# sparrow_v4_2.net
KiCad netlist of a schematic drawn in EAGLE
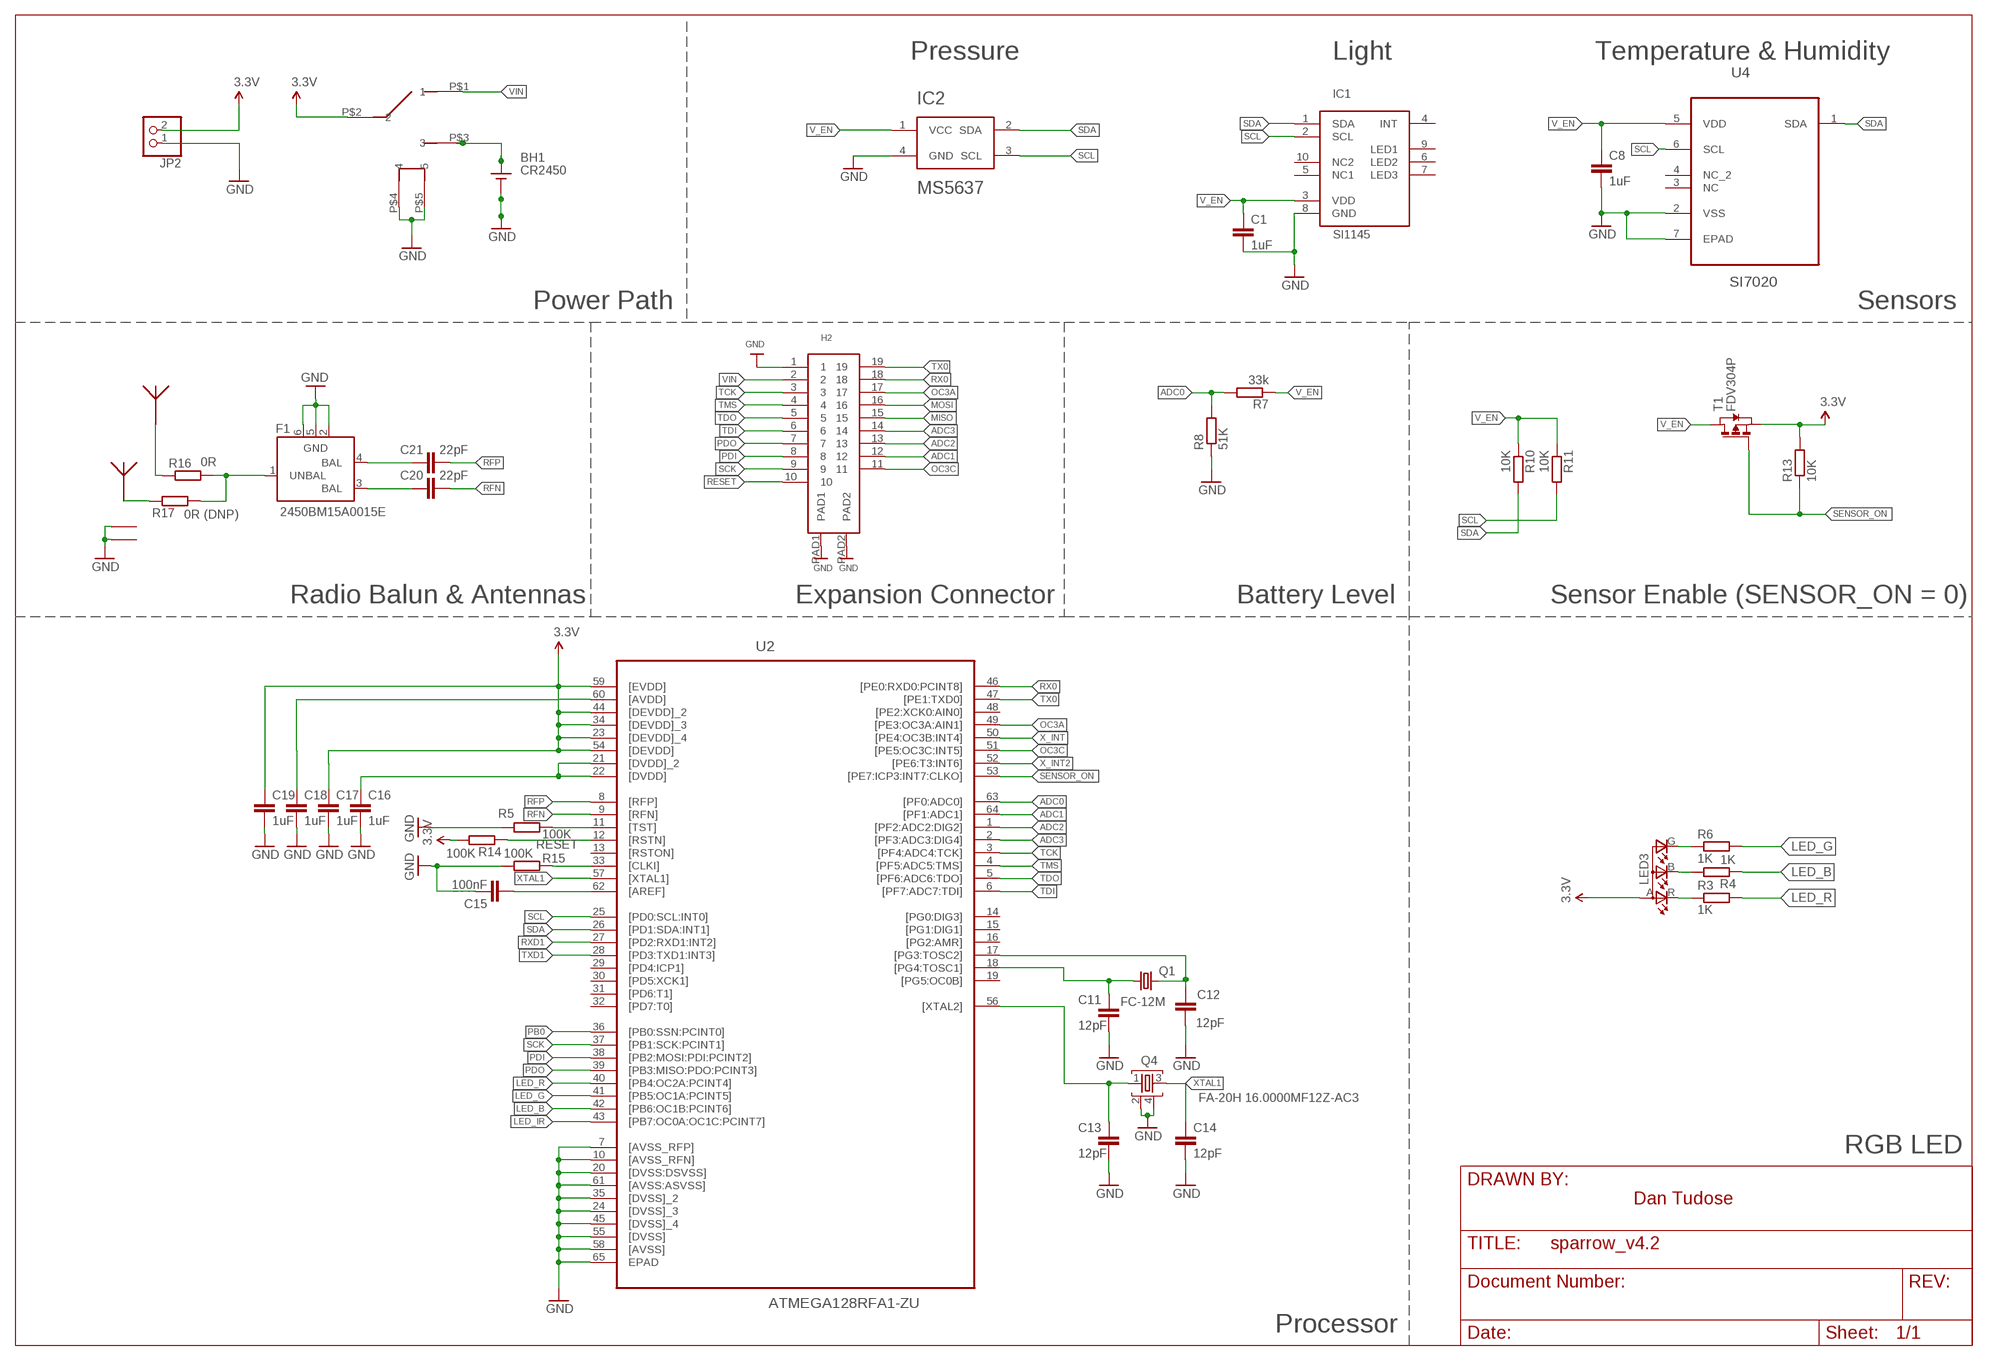
[diagram p0: schematic, sheet 1]

(export (version "E")
  (design (tool "Eeschema 10.0.6"))
  (components
    (comp (ref "C1")
      (value "1uF")
      (footprint "eagle-import:C0402")
      (libsource (lib "eagle-import") (part "C-EUC0402"))
    )
    (comp (ref "C8")
      (value "1uF")
      (footprint "eagle-import:C0402")
      (libsource (lib "eagle-import") (part "C-EUC0402"))
    )
    (comp (ref "C11")
      (value "12pF")
      (footprint "eagle-import:C0402")
      (libsource (lib "eagle-import") (part "C-EUC0402"))
    )
    (comp (ref "C12")
      (value "12pF")
      (footprint "eagle-import:C0402")
      (libsource (lib "eagle-import") (part "C-EUC0402"))
    )
    (comp (ref "C13")
      (value "12pF")
      (footprint "eagle-import:C0402")
      (libsource (lib "eagle-import") (part "C-EUC0402"))
    )
    (comp (ref "C14")
      (value "12pF")
      (footprint "eagle-import:C0402")
      (libsource (lib "eagle-import") (part "C-EUC0402"))
    )
    (comp (ref "C15")
      (value "100nF")
      (footprint "eagle-import:C0402")
      (libsource (lib "eagle-import") (part "C-EUC0402"))
    )
    (comp (ref "C16")
      (value "1uF")
      (footprint "eagle-import:C0402")
      (libsource (lib "eagle-import") (part "C-EUC0402"))
    )
    (comp (ref "C17")
      (value "1uF")
      (footprint "eagle-import:C0402")
      (libsource (lib "eagle-import") (part "C-EUC0402"))
    )
    (comp (ref "C18")
      (value "1uF")
      (footprint "eagle-import:C0402")
      (libsource (lib "eagle-import") (part "C-EUC0402"))
    )
    (comp (ref "C19")
      (value "1uF")
      (footprint "eagle-import:C0402")
      (libsource (lib "eagle-import") (part "C-EUC0402"))
    )
    (comp (ref "C20")
      (value "22pF")
      (footprint "eagle-import:C0402")
      (libsource (lib "eagle-import") (part "C-EUC0402"))
    )
    (comp (ref "C21")
      (value "22pF")
      (footprint "eagle-import:C0402")
      (libsource (lib "eagle-import") (part "C-EUC0402"))
    )
    (comp (ref "F1")
      (value "2450BM15A0015E")
      (footprint "eagle-import:2450BM15A0002")
      (libsource (lib "eagle-import") (part "2450BM15A0002"))
    )
    (comp (ref "H2")
      (value "DF9-19P-1V(32)")
      (footprint "eagle-import:DF9-19P-1V(32)")
      (libsource (lib "eagle-import") (part "DF9-19P-1V(32)"))
    )
    (comp (ref "IC1")
      (value "SI1145")
      (footprint "eagle-import:QFN10")
      (libsource (lib "eagle-import") (part "SI1145"))
    )
    (comp (ref "IC2")
      (value "MS5637")
      (footprint "eagle-import:MS5637")
      (libsource (lib "eagle-import") (part "MS5637"))
    )
    (comp (ref "JP2")
      (value "PINHD-1X2")
      (footprint "eagle-import:1X02")
      (libsource (lib "eagle-import") (part "PINHD-1X2"))
    )
    (comp (ref "LED3")
      (value "LED_RGB_CREE_PLCC4")
      (footprint "eagle-import:P-LCC-4-4")
      (libsource (lib "eagle-import") (part "LED_RGB_CREE_PLCC4"))
    )
    (comp (ref "Q1")
      (value "FC-12M")
      (footprint "eagle-import:FC-12M")
      (libsource (lib "eagle-import") (part "FC-12M"))
    )
    (comp (ref "Q4")
      (value "FA-20H 16.0000MF12Z-AC3")
      (footprint "eagle-import:FA-20H")
      (libsource (lib "eagle-import") (part "FA-20H"))
    )
    (comp (ref "R3")
      (value "1K")
      (footprint "eagle-import:R0402")
      (libsource (lib "eagle-import") (part "R-EU_R0402"))
    )
    (comp (ref "R4")
      (value "1K")
      (footprint "eagle-import:R0402")
      (libsource (lib "eagle-import") (part "R-EU_R0402"))
    )
    (comp (ref "R5")
      (value "100K")
      (footprint "eagle-import:R0402")
      (libsource (lib "eagle-import") (part "resistor_R-EU_R0402"))
    )
    (comp (ref "R6")
      (value "1K")
      (footprint "eagle-import:R0402")
      (libsource (lib "eagle-import") (part "R-EU_R0402"))
    )
    (comp (ref "R7")
      (value "33k")
      (footprint "eagle-import:R0402")
      (libsource (lib "eagle-import") (part "resistor_R-EU_R0402"))
    )
    (comp (ref "R8")
      (value "51K")
      (footprint "eagle-import:R0402")
      (libsource (lib "eagle-import") (part "resistor_R-EU_R0402"))
    )
    (comp (ref "R10")
      (value "10K")
      (footprint "eagle-import:R0402")
      (libsource (lib "eagle-import") (part "resistor_R-EU_R0402"))
    )
    (comp (ref "R11")
      (value "10K")
      (footprint "eagle-import:R0402")
      (libsource (lib "eagle-import") (part "resistor_R-EU_R0402"))
    )
    (comp (ref "R13")
      (value "10K")
      (footprint "eagle-import:R0402")
      (libsource (lib "eagle-import") (part "resistor_R-EU_R0402"))
    )
    (comp (ref "R14")
      (value "100K")
      (footprint "eagle-import:R0402")
      (libsource (lib "eagle-import") (part "resistor_R-EU_R0402"))
    )
    (comp (ref "R15")
      (value "100K")
      (footprint "eagle-import:R0402")
      (libsource (lib "eagle-import") (part "resistor_R-EU_R0402"))
    )
    (comp (ref "R16")
      (value "0R")
      (footprint "eagle-import:R0402")
      (libsource (lib "eagle-import") (part "resistor_R-EU_R0402"))
    )
    (comp (ref "R17")
      (value "0R (DNP)")
      (footprint "eagle-import:R0402")
      (libsource (lib "eagle-import") (part "resistor_R-EU_R0402"))
    )
    (comp (ref "T1")
      (value "FDV304P")
      (footprint "eagle-import:SOT-23")
      (libsource (lib "eagle-import") (part "PMOSSOT23"))
    )
    (comp (ref "U$1")
      (value "SWITCH")
      (footprint "eagle-import:PCM12")
      (libsource (lib "eagle-import") (part "SWITCH"))
    )
    (comp (ref "U1")
      (value "SMTU2450N-LF")
      (footprint "eagle-import:BATPACK")
      (libsource (lib "eagle-import") (part "RENATA_BAT"))
    )
    (comp (ref "U2")
      (value "ATMEGA128RFA1-ZU")
      (footprint "eagle-import:QFN50P900X900X90-64N")
      (libsource (lib "eagle-import") (part "ATMEGA128RFA1-ZU"))
    )
    (comp (ref "U4")
      (value "SI7020")
      (footprint "eagle-import:DFN300X300X110-7N")
      (fields (field (name "MPN") "SHT21"))
      (libsource (lib "eagle-import") (part "SHT21"))
    )
    (comp (ref "U8")
      (value "ANTENNA")
      (footprint "eagle-import:ANTPACK")
      (libsource (lib "eagle-import") (part "ANTENNA"))
    )
    (comp (ref "U10")
      (value "UFL-R-SMT")
      (footprint "eagle-import:U.FLPACK")
      (libsource (lib "eagle-import") (part "UFL-R-SMT"))
    )
  )
  (nets
    (net (code "1") (name "3.3V") (class "Default")
      (node (ref "C17") (pin "1") (pinfunction "1_1") (pintype "passive"))
      (node (ref "C19") (pin "1") (pinfunction "1_1") (pintype "passive"))
      (node (ref "JP2") (pin "2") (pinfunction "2_2") (pintype "passive"))
      (node (ref "LED3") (pin "A") (pinfunction "A2_A") (pintype "passive"))
      (node (ref "R13") (pin "2") (pinfunction "2_2") (pintype "passive"))
      (node (ref "R14") (pin "2") (pinfunction "2_2") (pintype "passive"))
      (node (ref "T1") (pin "2") (pinfunction "S_2") (pintype "passive"))
      (node (ref "U$1") (pin "P$2") (pinfunction "2_P$2") (pintype "bidirectional"))
      (node (ref "U2") (pin "23") (pinfunction "[DEVDD]_4_23") (pintype "power_in"))
      (node (ref "U2") (pin "34") (pinfunction "[DEVDD]_3_34") (pintype "power_in"))
      (node (ref "U2") (pin "44") (pinfunction "[DEVDD]_2_44") (pintype "power_in"))
      (node (ref "U2") (pin "54") (pinfunction "[DEVDD]_54") (pintype "power_in"))
      (node (ref "U2") (pin "59") (pinfunction "[EVDD]_59") (pintype "power_in"))
    )
    (net (code "2") (name "ADC0") (class "Default")
      (node (ref "R7") (pin "2") (pinfunction "2_2") (pintype "passive"))
      (node (ref "R8") (pin "2") (pinfunction "2_2") (pintype "passive"))
      (node (ref "U2") (pin "63") (pinfunction "[PF0:ADC0]_63") (pintype "bidirectional"))
    )
    (net (code "3") (name "ADC1") (class "Default")
      (node (ref "H2") (pin "12") (pinfunction "12_12") (pintype "bidirectional"))
      (node (ref "U2") (pin "64") (pinfunction "[PF1:ADC1]_64") (pintype "bidirectional"))
    )
    (net (code "4") (name "ADC2") (class "Default")
      (node (ref "H2") (pin "13") (pinfunction "13_13") (pintype "bidirectional"))
      (node (ref "U2") (pin "1") (pinfunction "[PF2:ADC2:DIG2]_1") (pintype "bidirectional"))
    )
    (net (code "5") (name "ADC3") (class "Default")
      (node (ref "H2") (pin "14") (pinfunction "14_14") (pintype "bidirectional"))
      (node (ref "U2") (pin "2") (pinfunction "[PF3:ADC3:DIG4]_2") (pintype "bidirectional"))
    )
    (net (code "6") (name "GND") (class "Default")
      (node (ref "C1") (pin "2") (pinfunction "2_2") (pintype "passive"))
      (node (ref "C11") (pin "2") (pinfunction "2_2") (pintype "passive"))
      (node (ref "C12") (pin "2") (pinfunction "2_2") (pintype "passive"))
      (node (ref "C13") (pin "2") (pinfunction "2_2") (pintype "passive"))
      (node (ref "C14") (pin "2") (pinfunction "2_2") (pintype "passive"))
      (node (ref "C15") (pin "1") (pinfunction "1_1") (pintype "passive"))
      (node (ref "C16") (pin "2") (pinfunction "2_2") (pintype "passive"))
      (node (ref "C17") (pin "2") (pinfunction "2_2") (pintype "passive"))
      (node (ref "C18") (pin "2") (pinfunction "2_2") (pintype "passive"))
      (node (ref "C19") (pin "2") (pinfunction "2_2") (pintype "passive"))
      (node (ref "C8") (pin "2") (pinfunction "2_2") (pintype "passive"))
      (node (ref "F1") (pin "2") (pinfunction "GND_2") (pintype "passive"))
      (node (ref "F1") (pin "5") (pinfunction "GND_5") (pintype "passive"))
      (node (ref "F1") (pin "6") (pinfunction "GND_6") (pintype "passive"))
      (node (ref "H2") (pin "1") (pinfunction "1_1") (pintype "bidirectional"))
      (node (ref "H2") (pin "PAD1") (pinfunction "PAD1_PAD1") (pintype "bidirectional"))
      (node (ref "H2") (pin "PAD2") (pinfunction "PAD2_PAD2") (pintype "bidirectional"))
      (node (ref "IC1") (pin "8") (pinfunction "GND_8") (pintype "bidirectional"))
      (node (ref "IC2") (pin "4") (pinfunction "GND_4") (pintype "bidirectional"))
      (node (ref "JP2") (pin "1") (pinfunction "1_1") (pintype "passive"))
      (node (ref "Q4") (pin "2") (pinfunction "2_2") (pintype "passive"))
      (node (ref "Q4") (pin "4") (pinfunction "4_4") (pintype "passive"))
      (node (ref "R15") (pin "2") (pinfunction "2_2") (pintype "passive"))
      (node (ref "R5") (pin "2") (pinfunction "2_2") (pintype "passive"))
      (node (ref "R8") (pin "1") (pinfunction "1_1") (pintype "passive"))
      (node (ref "U$1") (pin "P$4") (pinfunction "4_P$4") (pintype "bidirectional"))
      (node (ref "U$1") (pin "P$5") (pinfunction "5_P$5") (pintype "bidirectional"))
      (node (ref "U1") (pin "P$2") (pinfunction "P$2_P$2") (pintype "bidirectional"))
      (node (ref "U10") (pin "GND1") (pinfunction "P$3_GND1") (pintype "power_in"))
      (node (ref "U10") (pin "GND2") (pinfunction "P$2_GND2") (pintype "power_in"))
      (node (ref "U2") (pin "10") (pinfunction "[AVSS_RFN]_10") (pintype "power_in"))
      (node (ref "U2") (pin "20") (pinfunction "[DVSS:DSVSS]_20") (pintype "power_in"))
      (node (ref "U2") (pin "24") (pinfunction "[DVSS]_3_24") (pintype "power_in"))
      (node (ref "U2") (pin "35") (pinfunction "[DVSS]_2_35") (pintype "power_in"))
      (node (ref "U2") (pin "45") (pinfunction "[DVSS]_4_45") (pintype "power_in"))
      (node (ref "U2") (pin "55") (pinfunction "[DVSS]_55") (pintype "power_in"))
      (node (ref "U2") (pin "58") (pinfunction "[AVSS]_58") (pintype "power_in"))
      (node (ref "U2") (pin "61") (pinfunction "[AVSS:ASVSS]_61") (pintype "power_in"))
      (node (ref "U2") (pin "65") (pinfunction "EPAD_65") (pintype "passive"))
      (node (ref "U2") (pin "7") (pinfunction "[AVSS_RFP]_7") (pintype "power_in"))
      (node (ref "U4") (pin "2") (pinfunction "VSS_2") (pintype "power_in"))
      (node (ref "U4") (pin "7") (pinfunction "EPAD_7") (pintype "passive"))
    )
    (net (code "7") (name "LED_B") (class "Default")
      (node (ref "R4") (pin "1") (pinfunction "1_1") (pintype "passive"))
      (node (ref "U2") (pin "42") (pinfunction "[PB6:OC1B:PCINT6]_42") (pintype "bidirectional"))
    )
    (net (code "8") (name "LED_G") (class "Default")
      (node (ref "R6") (pin "2") (pinfunction "2_2") (pintype "passive"))
      (node (ref "U2") (pin "41") (pinfunction "[PB5:OC1A:PCINT5]_41") (pintype "bidirectional"))
    )
    (net (code "9") (name "LED_IR") (class "Default")
      (node (ref "U2") (pin "43") (pinfunction "[PB7:OC0A:OC1C:PCINT7]_43") (pintype "bidirectional"))
    )
    (net (code "10") (name "LED_R") (class "Default")
      (node (ref "R3") (pin "2") (pinfunction "2_2") (pintype "passive"))
      (node (ref "U2") (pin "40") (pinfunction "[PB4:OC2A:PCINT4]_40") (pintype "bidirectional"))
    )
    (net (code "11") (name "MISO") (class "Default")
      (node (ref "H2") (pin "15") (pinfunction "15_15") (pintype "bidirectional"))
    )
    (net (code "12") (name "MOSI") (class "Default")
      (node (ref "H2") (pin "16") (pinfunction "16_16") (pintype "bidirectional"))
    )
    (net (code "13") (name "Net-(C20-Pad1)") (class "Default")
      (node (ref "C20") (pin "1") (pinfunction "1_1") (pintype "passive"))
      (node (ref "F1") (pin "3") (pinfunction "BAL_3") (pintype "passive"))
    )
    (net (code "14") (name "Net-(C21-Pad1)") (class "Default")
      (node (ref "C21") (pin "1") (pinfunction "1_1") (pintype "passive"))
      (node (ref "F1") (pin "4") (pinfunction "BAL_4") (pintype "passive"))
    )
    (net (code "15") (name "Net-(F1-UNBAL)") (class "Default")
      (node (ref "F1") (pin "1") (pinfunction "UNBAL_1") (pintype "passive"))
      (node (ref "R16") (pin "2") (pinfunction "2_2") (pintype "passive"))
      (node (ref "R17") (pin "1") (pinfunction "1_1") (pintype "passive"))
    )
    (net (code "16") (name "Net-(LED3-CBLUE)") (class "Default")
      (node (ref "LED3") (pin "B") (pinfunction "CBLUE_B") (pintype "passive"))
      (node (ref "R4") (pin "2") (pinfunction "2_2") (pintype "passive"))
    )
    (net (code "17") (name "Net-(LED3-CGREEN)") (class "Default")
      (node (ref "LED3") (pin "G") (pinfunction "CGREEN_G") (pintype "passive"))
      (node (ref "R6") (pin "1") (pinfunction "1_1") (pintype "passive"))
    )
    (net (code "18") (name "Net-(LED3-CRED)") (class "Default")
      (node (ref "LED3") (pin "R") (pinfunction "CRED_R") (pintype "passive"))
      (node (ref "R3") (pin "1") (pinfunction "1_1") (pintype "passive"))
    )
    (net (code "19") (name "Net-(R16-Pad1)") (class "Default")
      (node (ref "R16") (pin "1") (pinfunction "1_1") (pintype "passive"))
      (node (ref "U8") (pin "P$1") (pinfunction "P$1_P$1") (pintype "bidirectional"))
    )
    (net (code "20") (name "Net-(R17-Pad2)") (class "Default")
      (node (ref "R17") (pin "2") (pinfunction "2_2") (pintype "passive"))
      (node (ref "U10") (pin "P$1") (pinfunction "P$1_P$1") (pintype "bidirectional"))
    )
    (net (code "21") (name "Net-(U$1-3)") (class "Default")
      (node (ref "U$1") (pin "P$3") (pinfunction "3_P$3") (pintype "bidirectional"))
      (node (ref "U1") (pin "P$1") (pinfunction "P$1_P$1") (pintype "bidirectional"))
    )
    (net (code "22") (name "Net-(U2-[AREF])") (class "Default")
      (node (ref "C15") (pin "2") (pinfunction "2_2") (pintype "passive"))
      (node (ref "U2") (pin "62") (pinfunction "[AREF]_62") (pintype "input"))
    )
    (net (code "23") (name "Net-(U2-[AVDD])") (class "Default")
      (node (ref "C18") (pin "1") (pinfunction "1_1") (pintype "passive"))
      (node (ref "U2") (pin "60") (pinfunction "[AVDD]_60") (pintype "power_in"))
    )
    (net (code "24") (name "Net-(U2-[CLKI])") (class "Default")
      (node (ref "R15") (pin "1") (pinfunction "1_1") (pintype "passive"))
      (node (ref "U2") (pin "33") (pinfunction "[CLKI]_33") (pintype "input"))
    )
    (net (code "25") (name "Net-(U2-[DVDD])") (class "Default")
      (node (ref "C16") (pin "1") (pinfunction "1_1") (pintype "passive"))
      (node (ref "U2") (pin "21") (pinfunction "[DVDD]_2_21") (pintype "power_in"))
      (node (ref "U2") (pin "22") (pinfunction "[DVDD]_22") (pintype "power_in"))
    )
    (net (code "26") (name "Net-(U2-[PG3:TOSC2])") (class "Default")
      (node (ref "C12") (pin "1") (pinfunction "1_1") (pintype "passive"))
      (node (ref "Q1") (pin "2") (pinfunction "2_2") (pintype "passive"))
      (node (ref "U2") (pin "17") (pinfunction "[PG3:TOSC2]_17") (pintype "bidirectional"))
    )
    (net (code "27") (name "Net-(U2-[PG4:TOSC1])") (class "Default")
      (node (ref "C11") (pin "1") (pinfunction "1_1") (pintype "passive"))
      (node (ref "Q1") (pin "1") (pinfunction "1_1") (pintype "passive"))
      (node (ref "U2") (pin "18") (pinfunction "[PG4:TOSC1]_18") (pintype "bidirectional"))
    )
    (net (code "28") (name "Net-(U2-[TST])") (class "Default")
      (node (ref "R5") (pin "1") (pinfunction "1_1") (pintype "passive"))
      (node (ref "U2") (pin "11") (pinfunction "[TST]_11") (pintype "input"))
    )
    (net (code "29") (name "Net-(U2-[XTAL2])") (class "Default")
      (node (ref "C13") (pin "1") (pinfunction "1_1") (pintype "passive"))
      (node (ref "Q4") (pin "1") (pinfunction "1_1") (pintype "passive"))
      (node (ref "U2") (pin "56") (pinfunction "[XTAL2]_56") (pintype "output"))
    )
    (net (code "30") (name "OC3A") (class "Default")
      (node (ref "H2") (pin "17") (pinfunction "17_17") (pintype "bidirectional"))
      (node (ref "U2") (pin "49") (pinfunction "[PE3:OC3A:AIN1]_49") (pintype "bidirectional"))
    )
    (net (code "31") (name "OC3C") (class "Default")
      (node (ref "H2") (pin "11") (pinfunction "11_11") (pintype "bidirectional"))
      (node (ref "U2") (pin "51") (pinfunction "[PE5:OC3C:INT5]_51") (pintype "bidirectional"))
    )
    (net (code "32") (name "PB0") (class "Default")
      (node (ref "U2") (pin "36") (pinfunction "[PB0:SSN:PCINT0]_36") (pintype "bidirectional"))
    )
    (net (code "33") (name "PDI") (class "Default")
      (node (ref "H2") (pin "8") (pinfunction "8_8") (pintype "bidirectional"))
      (node (ref "U2") (pin "38") (pinfunction "[PB2:MOSI:PDI:PCINT2]_38") (pintype "bidirectional"))
    )
    (net (code "34") (name "PDO") (class "Default")
      (node (ref "H2") (pin "7") (pinfunction "7_7") (pintype "bidirectional"))
      (node (ref "U2") (pin "39") (pinfunction "[PB3:MISO:PDO:PCINT3]_39") (pintype "bidirectional"))
    )
    (net (code "35") (name "RESET") (class "Default")
      (node (ref "H2") (pin "10") (pinfunction "10_10") (pintype "bidirectional"))
      (node (ref "R14") (pin "1") (pinfunction "1_1") (pintype "passive"))
      (node (ref "U2") (pin "12") (pinfunction "[RSTN]_12") (pintype "input"))
    )
    (net (code "36") (name "RFN") (class "Default")
      (node (ref "C20") (pin "2") (pinfunction "2_2") (pintype "passive"))
      (node (ref "U2") (pin "9") (pinfunction "[RFN]_9") (pintype "input"))
    )
    (net (code "37") (name "RFP") (class "Default")
      (node (ref "C21") (pin "2") (pinfunction "2_2") (pintype "passive"))
      (node (ref "U2") (pin "8") (pinfunction "[RFP]_8") (pintype "input"))
    )
    (net (code "38") (name "RX0") (class "Default")
      (node (ref "H2") (pin "18") (pinfunction "18_18") (pintype "bidirectional"))
      (node (ref "U2") (pin "46") (pinfunction "[PE0:RXD0:PCINT8]_46") (pintype "bidirectional"))
    )
    (net (code "39") (name "RXD1") (class "Default")
      (node (ref "U2") (pin "27") (pinfunction "[PD2:RXD1:INT2]_27") (pintype "bidirectional"))
    )
    (net (code "40") (name "SCK") (class "Default")
      (node (ref "H2") (pin "9") (pinfunction "9_9") (pintype "bidirectional"))
      (node (ref "U2") (pin "37") (pinfunction "[PB1:SCK:PCINT1]_37") (pintype "bidirectional"))
    )
    (net (code "41") (name "SCL") (class "Default")
      (node (ref "IC1") (pin "2") (pinfunction "SCL_2") (pintype "bidirectional"))
      (node (ref "IC2") (pin "3") (pinfunction "SCL_3") (pintype "bidirectional"))
      (node (ref "R11") (pin "2") (pinfunction "2_2") (pintype "passive"))
      (node (ref "U2") (pin "25") (pinfunction "[PD0:SCL:INT0]_25") (pintype "bidirectional"))
      (node (ref "U4") (pin "6") (pinfunction "SCL_6") (pintype "input"))
    )
    (net (code "42") (name "SDA") (class "Default")
      (node (ref "IC1") (pin "1") (pinfunction "SDA_1") (pintype "bidirectional"))
      (node (ref "IC2") (pin "2") (pinfunction "SDA_2") (pintype "bidirectional"))
      (node (ref "R10") (pin "2") (pinfunction "2_2") (pintype "passive"))
      (node (ref "U2") (pin "26") (pinfunction "[PD1:SDA:INT1]_26") (pintype "bidirectional"))
      (node (ref "U4") (pin "1") (pinfunction "SDA_1") (pintype "bidirectional"))
    )
    (net (code "43") (name "SENSOR_ON") (class "Default")
      (node (ref "R13") (pin "1") (pinfunction "1_1") (pintype "passive"))
      (node (ref "T1") (pin "3") (pinfunction "G_3") (pintype "passive"))
      (node (ref "U2") (pin "53") (pinfunction "[PE7:ICP3:INT7:CLKO]_53") (pintype "bidirectional"))
    )
    (net (code "44") (name "TCK") (class "Default")
      (node (ref "H2") (pin "3") (pinfunction "3_3") (pintype "bidirectional"))
      (node (ref "U2") (pin "3") (pinfunction "[PF4:ADC4:TCK]_3") (pintype "bidirectional"))
    )
    (net (code "45") (name "TDI") (class "Default")
      (node (ref "H2") (pin "6") (pinfunction "6_6") (pintype "bidirectional"))
      (node (ref "U2") (pin "6") (pinfunction "[PF7:ADC7:TDI]_6") (pintype "bidirectional"))
    )
    (net (code "46") (name "TDO") (class "Default")
      (node (ref "H2") (pin "5") (pinfunction "5_5") (pintype "bidirectional"))
      (node (ref "U2") (pin "5") (pinfunction "[PF6:ADC6:TDO]_5") (pintype "bidirectional"))
    )
    (net (code "47") (name "TMS") (class "Default")
      (node (ref "H2") (pin "4") (pinfunction "4_4") (pintype "bidirectional"))
      (node (ref "U2") (pin "4") (pinfunction "[PF5:ADC5:TMS]_4") (pintype "bidirectional"))
    )
    (net (code "48") (name "TX0") (class "Default")
      (node (ref "H2") (pin "19") (pinfunction "19_19") (pintype "bidirectional"))
      (node (ref "U2") (pin "47") (pinfunction "[PE1:TXD0]_47") (pintype "bidirectional"))
    )
    (net (code "49") (name "TXD1") (class "Default")
      (node (ref "U2") (pin "28") (pinfunction "[PD3:TXD1:INT3]_28") (pintype "bidirectional"))
    )
    (net (code "50") (name "VIN") (class "Default")
      (node (ref "H2") (pin "2") (pinfunction "2_2") (pintype "bidirectional"))
      (node (ref "U$1") (pin "P$1") (pinfunction "1_P$1") (pintype "bidirectional"))
    )
    (net (code "51") (name "V_EN") (class "Default")
      (node (ref "C1") (pin "1") (pinfunction "1_1") (pintype "passive"))
      (node (ref "C8") (pin "1") (pinfunction "1_1") (pintype "passive"))
      (node (ref "IC1") (pin "3") (pinfunction "VDD_3") (pintype "bidirectional"))
      (node (ref "IC2") (pin "1") (pinfunction "VCC_1") (pintype "bidirectional"))
      (node (ref "R10") (pin "1") (pinfunction "1_1") (pintype "passive"))
      (node (ref "R11") (pin "1") (pinfunction "1_1") (pintype "passive"))
      (node (ref "R7") (pin "1") (pinfunction "1_1") (pintype "passive"))
      (node (ref "T1") (pin "1") (pinfunction "D_1") (pintype "passive"))
      (node (ref "U4") (pin "5") (pinfunction "VDD_5") (pintype "power_in"))
    )
    (net (code "52") (name "XTAL1") (class "Default")
      (node (ref "C14") (pin "1") (pinfunction "1_1") (pintype "passive"))
      (node (ref "Q4") (pin "3") (pinfunction "3_3") (pintype "passive"))
      (node (ref "U2") (pin "57") (pinfunction "[XTAL1]_57") (pintype "input"))
    )
    (net (code "53") (name "X_INT") (class "Default")
      (node (ref "U2") (pin "50") (pinfunction "[PE4:OC3B:INT4]_50") (pintype "bidirectional"))
    )
    (net (code "54") (name "X_INT2") (class "Default")
      (node (ref "U2") (pin "52") (pinfunction "[PE6:T3:INT6]_52") (pintype "bidirectional"))
    )
    (net (code "55") (name "unconnected-(IC1-INT-Pad4)") (class "Default")
      (node (ref "IC1") (pin "4") (pinfunction "INT_4") (pintype "bidirectional"))
    )
    (net (code "56") (name "unconnected-(IC1-LED1-Pad9)") (class "Default")
      (node (ref "IC1") (pin "9") (pinfunction "LED1_9") (pintype "bidirectional"))
    )
    (net (code "57") (name "unconnected-(IC1-LED2-Pad6)") (class "Default")
      (node (ref "IC1") (pin "6") (pinfunction "LED2_6") (pintype "bidirectional"))
    )
    (net (code "58") (name "unconnected-(IC1-LED3-Pad7)") (class "Default")
      (node (ref "IC1") (pin "7") (pinfunction "LED3_7") (pintype "bidirectional"))
    )
    (net (code "59") (name "unconnected-(IC1-NC1-Pad5)") (class "Default")
      (node (ref "IC1") (pin "5") (pinfunction "NC1_5") (pintype "no_connect"))
    )
    (net (code "60") (name "unconnected-(IC1-NC2-Pad10)") (class "Default")
      (node (ref "IC1") (pin "10") (pinfunction "NC2_10") (pintype "no_connect"))
    )
    (net (code "61") (name "unconnected-(U2-[PD4:ICP1]-Pad29)") (class "Default")
      (node (ref "U2") (pin "29") (pinfunction "[PD4:ICP1]_29") (pintype "bidirectional"))
    )
    (net (code "62") (name "unconnected-(U2-[PD5:XCK1]-Pad30)") (class "Default")
      (node (ref "U2") (pin "30") (pinfunction "[PD5:XCK1]_30") (pintype "bidirectional"))
    )
    (net (code "63") (name "unconnected-(U2-[PD6:T1]-Pad31)") (class "Default")
      (node (ref "U2") (pin "31") (pinfunction "[PD6:T1]_31") (pintype "bidirectional"))
    )
    (net (code "64") (name "unconnected-(U2-[PD7:T0]-Pad32)") (class "Default")
      (node (ref "U2") (pin "32") (pinfunction "[PD7:T0]_32") (pintype "bidirectional"))
    )
    (net (code "65") (name "unconnected-(U2-[PE2:XCK0:AIN0]-Pad48)") (class "Default")
      (node (ref "U2") (pin "48") (pinfunction "[PE2:XCK0:AIN0]_48") (pintype "bidirectional"))
    )
    (net (code "66") (name "unconnected-(U2-[PG0:DIG3]-Pad14)") (class "Default")
      (node (ref "U2") (pin "14") (pinfunction "[PG0:DIG3]_14") (pintype "bidirectional"))
    )
    (net (code "67") (name "unconnected-(U2-[PG1:DIG1]-Pad15)") (class "Default")
      (node (ref "U2") (pin "15") (pinfunction "[PG1:DIG1]_15") (pintype "bidirectional"))
    )
    (net (code "68") (name "unconnected-(U2-[PG2:AMR]-Pad16)") (class "Default")
      (node (ref "U2") (pin "16") (pinfunction "[PG2:AMR]_16") (pintype "bidirectional"))
    )
    (net (code "69") (name "unconnected-(U2-[PG5:OC0B]-Pad19)") (class "Default")
      (node (ref "U2") (pin "19") (pinfunction "[PG5:OC0B]_19") (pintype "bidirectional"))
    )
    (net (code "70") (name "unconnected-(U2-[RSTON]-Pad13)") (class "Default")
      (node (ref "U2") (pin "13") (pinfunction "[RSTON]_13") (pintype "input"))
    )
    (net (code "71") (name "unconnected-(U4-NC-Pad3)") (class "Default")
      (node (ref "U4") (pin "3") (pinfunction "NC_3") (pintype "no_connect"))
    )
    (net (code "72") (name "unconnected-(U4-NC_2-Pad4)") (class "Default")
      (node (ref "U4") (pin "4") (pinfunction "NC_2_4") (pintype "no_connect"))
    )
  )
)
